# controllerHat.net
KiCad netlist of a schematic drawn in EAGLE
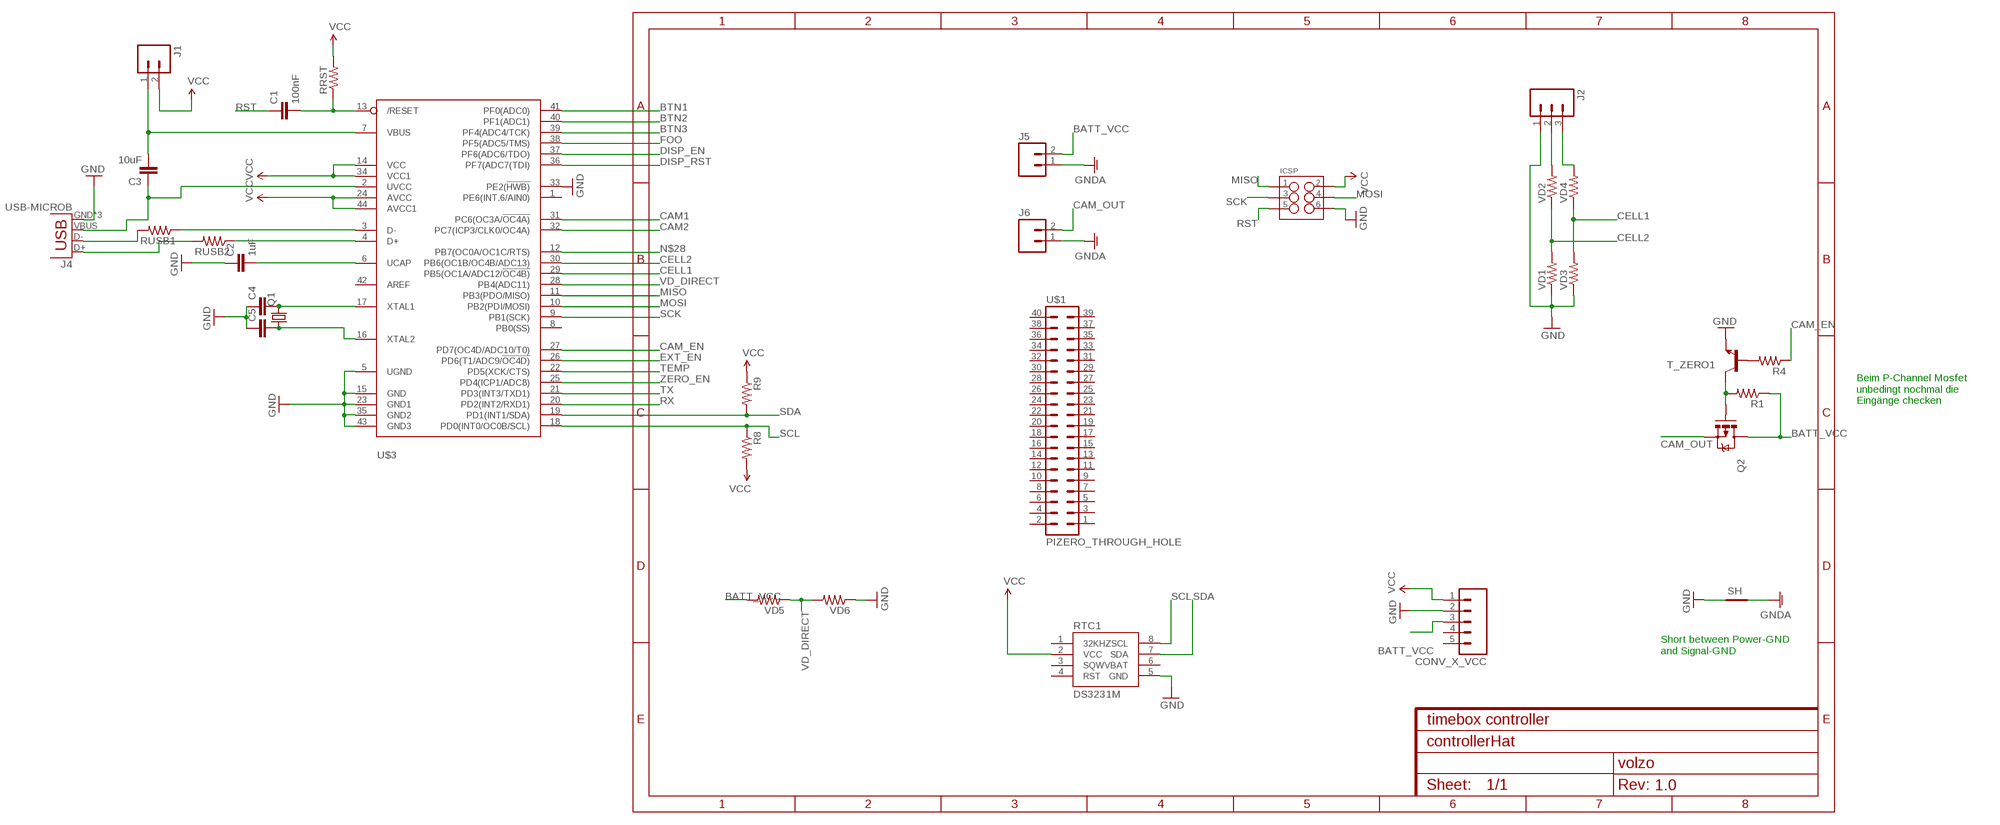
[diagram p0: schematic, sheet 1]

(export (version "E")
  (design (tool "Eeschema 10.0.6"))
  (components
    (comp (ref "C1")
      (value "100nF")
      (footprint "eagle-import:1206")
      (libsource (lib "eagle-import") (part "SparkFun-Passives_CAP1206"))
    )
    (comp (ref "C2")
      (value "1uF")
      (footprint "eagle-import:1206")
      (libsource (lib "eagle-import") (part "CAP1206"))
    )
    (comp (ref "C3")
      (value "10uF")
      (footprint "eagle-import:1206")
      (libsource (lib "eagle-import") (part "SparkFun-Passives_CAP1206"))
    )
    (comp (ref "C4")
      (value "CAP1206")
      (footprint "eagle-import:1206")
      (libsource (lib "eagle-import") (part "SparkFun-Passives_CAP1206"))
    )
    (comp (ref "C5")
      (value "CAP1206")
      (footprint "eagle-import:1206")
      (libsource (lib "eagle-import") (part "SparkFun-Passives_CAP1206"))
    )
    (comp (ref "CONV_X_VCC")
      (value "M05LOCK")
      (footprint "eagle-import:1X05_LOCK")
      (libsource (lib "eagle-import") (part "M05LOCK"))
    )
    (comp (ref "ICSP")
      (value "M03X2FEMALE")
      (footprint "eagle-import:2X3")
      (libsource (lib "eagle-import") (part "M03X2FEMALE"))
    )
    (comp (ref "J1")
      (value "M02LOCK")
      (footprint "eagle-import:1X02_LOCK")
      (libsource (lib "eagle-import") (part "M02LOCK"))
    )
    (comp (ref "J2")
      (value "M03LOCK")
      (footprint "eagle-import:1X03_LOCK")
      (libsource (lib "eagle-import") (part "M03LOCK"))
    )
    (comp (ref "J4")
      (value "USB-MICROB")
      (footprint "eagle-import:USB-MICROB")
      (libsource (lib "eagle-import") (part "USB-MICROB"))
    )
    (comp (ref "J5")
      (value "M023.5MM_LOCK")
      (footprint "eagle-import:SCREWTERMINAL-3.5MM-2_LOCK")
      (libsource (lib "eagle-import") (part "M023.5MM_LOCK"))
    )
    (comp (ref "J6")
      (value "M023.5MM_LOCK")
      (footprint "eagle-import:SCREWTERMINAL-3.5MM-2_LOCK")
      (libsource (lib "eagle-import") (part "M023.5MM_LOCK"))
    )
    (comp (ref "Q1")
      (value "CRYSTALMM20SS")
      (footprint "eagle-import:MM20SS")
      (libsource (lib "eagle-import") (part "CRYSTALMM20SS"))
    )
    (comp (ref "Q2")
      (value "MOSFET-PCHANNELNDP6020P_20V_24A_LOW_VGS_TH")
      (footprint "eagle-import:TO220V")
      (libsource (lib "eagle-import") (part "MOSFET-PCHANNELNDP6020P_20V_24A_LOW_VGS_TH"))
    )
    (comp (ref "R1")
      (value "RESISTOR1206")
      (footprint "eagle-import:1206")
      (libsource (lib "eagle-import") (part "RESISTOR1206"))
    )
    (comp (ref "R4")
      (value "RESISTOR1206")
      (footprint "eagle-import:1206")
      (libsource (lib "eagle-import") (part "RESISTOR1206"))
    )
    (comp (ref "R8")
      (value "RESISTOR1206")
      (footprint "eagle-import:1206")
      (libsource (lib "eagle-import") (part "RESISTOR1206"))
    )
    (comp (ref "R9")
      (value "RESISTOR1206")
      (footprint "eagle-import:1206")
      (libsource (lib "eagle-import") (part "RESISTOR1206"))
    )
    (comp (ref "RRST")
      (value "RESISTOR1206")
      (footprint "eagle-import:1206")
      (libsource (lib "eagle-import") (part "RESISTOR1206"))
    )
    (comp (ref "RTC1")
      (value "DS3231M")
      (footprint "eagle-import:SOIC8")
      (libsource (lib "eagle-import") (part "DS3231M"))
    )
    (comp (ref "RUSB1")
      (value "RESISTOR1206")
      (footprint "eagle-import:1206")
      (libsource (lib "eagle-import") (part "RESISTOR1206"))
    )
    (comp (ref "RUSB2")
      (value "RESISTOR1206")
      (footprint "eagle-import:1206")
      (libsource (lib "eagle-import") (part "RESISTOR1206"))
    )
    (comp (ref "SH")
      (value "SHORT-HT5")
      (footprint "eagle-import:SHORT_TOP-50")
      (libsource (lib "eagle-import") (part "SHORT-HT5"))
    )
    (comp (ref "T_ZERO1")
      (value "TRANSISTOR_NPN2N3904")
      (footprint "eagle-import:TO-92")
      (libsource (lib "eagle-import") (part "TRANSISTOR_NPN2N3904"))
    )
    (comp (ref "U$1")
      (value "PIZERO_THROUGH_HOLE")
      (footprint "eagle-import:PIZERO_THOUGH_HOLE")
      (libsource (lib "eagle-import") (part "PIZERO_THROUGH_HOLE"))
    )
    (comp (ref "U$3")
      (value "ATMEGA32U4-AU")
      (footprint "eagle-import:TQFP44")
      (libsource (lib "eagle-import") (part "ATMEGA32U4-AU"))
    )
    (comp (ref "VD1")
      (value "RESISTOR1206")
      (footprint "eagle-import:1206")
      (libsource (lib "eagle-import") (part "RESISTOR1206"))
    )
    (comp (ref "VD2")
      (value "RESISTOR1206")
      (footprint "eagle-import:1206")
      (libsource (lib "eagle-import") (part "RESISTOR1206"))
    )
    (comp (ref "VD3")
      (value "RESISTOR1206")
      (footprint "eagle-import:1206")
      (libsource (lib "eagle-import") (part "RESISTOR1206"))
    )
    (comp (ref "VD4")
      (value "RESISTOR1206")
      (footprint "eagle-import:1206")
      (libsource (lib "eagle-import") (part "RESISTOR1206"))
    )
    (comp (ref "VD5")
      (value "RESISTOR1206")
      (footprint "eagle-import:1206")
      (libsource (lib "eagle-import") (part "RESISTOR1206"))
    )
    (comp (ref "VD6")
      (value "RESISTOR1206")
      (footprint "eagle-import:1206")
      (libsource (lib "eagle-import") (part "RESISTOR1206"))
    )
  )
  (nets
    (net (code "1") (name "/BATT_VCC") (class "Default")
      (node (ref "CONV_X_VCC") (pin "3") (pinfunction "3_3") (pintype "passive"))
      (node (ref "J5") (pin "2") (pinfunction "2_2") (pintype "passive"))
      (node (ref "Q2") (pin "2") (pinfunction "D_2") (pintype "passive"))
      (node (ref "R1") (pin "1") (pinfunction "1_1") (pintype "passive"))
      (node (ref "VD5") (pin "2") (pinfunction "2_2") (pintype "passive"))
    )
    (net (code "2") (name "/BTN1") (class "Default")
      (node (ref "U$3") (pin "41") (pinfunction "PF0(ADC0)_41") (pintype "bidirectional"))
    )
    (net (code "3") (name "/BTN2") (class "Default")
      (node (ref "U$3") (pin "40") (pinfunction "PF1(ADC1)_40") (pintype "bidirectional"))
    )
    (net (code "4") (name "/BTN3") (class "Default")
      (node (ref "U$3") (pin "39") (pinfunction "PF4(ADC4/TCK)_39") (pintype "bidirectional"))
    )
    (net (code "5") (name "/CAM1") (class "Default")
      (node (ref "U$3") (pin "31") (pinfunction "PC6(OC3A/~{OC4A})_31") (pintype "bidirectional"))
    )
    (net (code "6") (name "/CAM2") (class "Default")
      (node (ref "U$3") (pin "32") (pinfunction "PC7(ICP3/CLK0/OC4A)_32") (pintype "bidirectional"))
    )
    (net (code "7") (name "/CAM_EN") (class "Default")
      (node (ref "R4") (pin "1") (pinfunction "1_1") (pintype "passive"))
      (node (ref "U$3") (pin "27") (pinfunction "PD7(OC4D/ADC10/T0)_27") (pintype "bidirectional"))
    )
    (net (code "8") (name "/CAM_OUT") (class "Default")
      (node (ref "J6") (pin "2") (pinfunction "2_2") (pintype "passive"))
      (node (ref "Q2") (pin "3") (pinfunction "S_3") (pintype "passive"))
    )
    (net (code "9") (name "/CELL1") (class "Default")
      (node (ref "U$3") (pin "29") (pinfunction "PB5(OC1A/ADC12/~{OC4B})_29") (pintype "bidirectional"))
      (node (ref "VD3") (pin "2") (pinfunction "2_2") (pintype "passive"))
      (node (ref "VD4") (pin "1") (pinfunction "1_1") (pintype "passive"))
    )
    (net (code "10") (name "/CELL2") (class "Default")
      (node (ref "U$3") (pin "30") (pinfunction "PB6(OC1B/OC4B/ADC13)_30") (pintype "bidirectional"))
      (node (ref "VD1") (pin "2") (pinfunction "2_2") (pintype "passive"))
      (node (ref "VD2") (pin "1") (pinfunction "1_1") (pintype "passive"))
    )
    (net (code "11") (name "/DISP_EN") (class "Default")
      (node (ref "U$3") (pin "37") (pinfunction "PF6(ADC6/TDO)_37") (pintype "bidirectional"))
    )
    (net (code "12") (name "/DISP_RST") (class "Default")
      (node (ref "U$3") (pin "36") (pinfunction "PF7(ADC7(TDI)_36") (pintype "bidirectional"))
    )
    (net (code "13") (name "/EXT_EN") (class "Default")
      (node (ref "U$3") (pin "26") (pinfunction "PD6(T1/ADC9/~{OC4D})_26") (pintype "bidirectional"))
    )
    (net (code "14") (name "/FOO") (class "Default")
      (node (ref "U$3") (pin "38") (pinfunction "PF5(ADC5/TMS)_38") (pintype "bidirectional"))
    )
    (net (code "15") (name "/MISO") (class "Default")
      (node (ref "ICSP") (pin "1") (pinfunction "1_1") (pintype "bidirectional"))
      (node (ref "U$3") (pin "11") (pinfunction "PB3(PDO/MISO)_11") (pintype "bidirectional"))
    )
    (net (code "16") (name "/MOSI") (class "Default")
      (node (ref "ICSP") (pin "4") (pinfunction "4_4") (pintype "bidirectional"))
      (node (ref "U$3") (pin "10") (pinfunction "PB2(PDI/MOSI)_10") (pintype "bidirectional"))
    )
    (net (code "17") (name "/N$28") (class "Default")
      (node (ref "U$3") (pin "12") (pinfunction "PB7(OC0A/OC1C/RTS)_12") (pintype "bidirectional"))
    )
    (net (code "18") (name "/RST") (class "Default")
      (node (ref "C1") (pin "1") (pinfunction "1_1") (pintype "passive"))
      (node (ref "ICSP") (pin "5") (pinfunction "5_5") (pintype "bidirectional"))
    )
    (net (code "19") (name "/RX") (class "Default")
      (node (ref "U$3") (pin "20") (pinfunction "PD2(INT2/RXD1)_20") (pintype "bidirectional"))
    )
    (net (code "20") (name "/SCK") (class "Default")
      (node (ref "ICSP") (pin "3") (pinfunction "3_3") (pintype "bidirectional"))
      (node (ref "U$3") (pin "9") (pinfunction "PB1(SCK)_9") (pintype "bidirectional"))
    )
    (net (code "21") (name "/SCL") (class "Default")
      (node (ref "R8") (pin "1") (pinfunction "1_1") (pintype "passive"))
      (node (ref "RTC1") (pin "8") (pinfunction "SCL_8") (pintype "bidirectional"))
      (node (ref "U$3") (pin "18") (pinfunction "PD0(INT0/OC0B/SCL)_18") (pintype "bidirectional"))
    )
    (net (code "22") (name "/SDA") (class "Default")
      (node (ref "R9") (pin "2") (pinfunction "2_2") (pintype "passive"))
      (node (ref "RTC1") (pin "7") (pinfunction "SDA_7") (pintype "bidirectional"))
      (node (ref "U$3") (pin "19") (pinfunction "PD1(INT1/SDA)_19") (pintype "bidirectional"))
    )
    (net (code "23") (name "/TEMP") (class "Default")
      (node (ref "U$3") (pin "22") (pinfunction "PD5(XCK/CTS)_22") (pintype "bidirectional"))
    )
    (net (code "24") (name "/TX") (class "Default")
      (node (ref "U$3") (pin "21") (pinfunction "PD3(INT3/TXD1)_21") (pintype "bidirectional"))
    )
    (net (code "25") (name "/VBAT") (class "Default")
      (node (ref "RTC1") (pin "6") (pinfunction "VBAT_6") (pintype "power_in"))
    )
    (net (code "26") (name "/VD_DIRECT") (class "Default")
      (node (ref "U$3") (pin "28") (pinfunction "PB4(ADC11)_28") (pintype "bidirectional"))
      (node (ref "VD5") (pin "1") (pinfunction "1_1") (pintype "passive"))
      (node (ref "VD6") (pin "2") (pinfunction "2_2") (pintype "passive"))
    )
    (net (code "27") (name "/ZERO_EN") (class "Default")
      (node (ref "U$3") (pin "25") (pinfunction "PD4(ICP1/ADC8)_25") (pintype "bidirectional"))
    )
    (net (code "28") (name "GND") (class "Default")
      (node (ref "C2") (pin "1") (pinfunction "1_1") (pintype "passive"))
      (node (ref "C4") (pin "1") (pinfunction "1_1") (pintype "passive"))
      (node (ref "C5") (pin "1") (pinfunction "1_1") (pintype "passive"))
      (node (ref "CONV_X_VCC") (pin "2") (pinfunction "2_2") (pintype "passive"))
      (node (ref "ICSP") (pin "6") (pinfunction "6_6") (pintype "bidirectional"))
      (node (ref "J2") (pin "1") (pinfunction "1_1") (pintype "passive"))
      (node (ref "J4") (pin "GND") (pinfunction "GND_GND") (pintype "bidirectional"))
      (node (ref "J4") (pin "MT1") (pinfunction "GND_MT1") (pintype "bidirectional"))
      (node (ref "J4") (pin "MT2") (pinfunction "GND_MT2") (pintype "bidirectional"))
      (node (ref "RTC1") (pin "5") (pinfunction "GND_5") (pintype "power_in"))
      (node (ref "SH") (pin "1") (pinfunction "P$1_1") (pintype "bidirectional"))
      (node (ref "T_ZERO1") (pin "1") (pinfunction "E_1") (pintype "passive"))
      (node (ref "U$3") (pin "15") (pinfunction "GND_15") (pintype "bidirectional"))
      (node (ref "U$3") (pin "23") (pinfunction "GND1_23") (pintype "bidirectional"))
      (node (ref "U$3") (pin "33") (pinfunction "PE2(~{HWB})_33") (pintype "bidirectional"))
      (node (ref "U$3") (pin "35") (pinfunction "GND2_35") (pintype "bidirectional"))
      (node (ref "U$3") (pin "43") (pinfunction "GND3_43") (pintype "bidirectional"))
      (node (ref "U$3") (pin "5") (pinfunction "UGND_5") (pintype "bidirectional"))
      (node (ref "VD1") (pin "1") (pinfunction "1_1") (pintype "passive"))
      (node (ref "VD3") (pin "1") (pinfunction "1_1") (pintype "passive"))
      (node (ref "VD6") (pin "1") (pinfunction "1_1") (pintype "passive"))
    )
    (net (code "29") (name "GNDA") (class "Default")
      (node (ref "J5") (pin "1") (pinfunction "1_1") (pintype "passive"))
      (node (ref "J6") (pin "1") (pinfunction "1_1") (pintype "passive"))
      (node (ref "SH") (pin "2") (pinfunction "P$2_2") (pintype "bidirectional"))
    )
    (net (code "30") (name "Net-(J2-Pad2)") (class "Default")
      (node (ref "J2") (pin "2") (pinfunction "2_2") (pintype "passive"))
      (node (ref "VD2") (pin "2") (pinfunction "2_2") (pintype "passive"))
    )
    (net (code "31") (name "Net-(J2-Pad3)") (class "Default")
      (node (ref "J2") (pin "3") (pinfunction "3_3") (pintype "passive"))
      (node (ref "VD4") (pin "2") (pinfunction "2_2") (pintype "passive"))
    )
    (net (code "32") (name "Net-(J4-PadD+)") (class "Default")
      (node (ref "J4") (pin "D+") (pinfunction "D+_D+") (pintype "bidirectional"))
      (node (ref "RUSB2") (pin "2") (pinfunction "2_2") (pintype "passive"))
    )
    (net (code "33") (name "Net-(J4-PadD-)") (class "Default")
      (node (ref "J4") (pin "D-") (pinfunction "D-_D-") (pintype "bidirectional"))
      (node (ref "RUSB1") (pin "2") (pinfunction "2_2") (pintype "passive"))
    )
    (net (code "34") (name "Net-(Q1-2)") (class "Default")
      (node (ref "C4") (pin "2") (pinfunction "2_2") (pintype "passive"))
      (node (ref "Q1") (pin "4") (pinfunction "2_4") (pintype "passive"))
      (node (ref "U$3") (pin "17") (pinfunction "XTAL1_17") (pintype "bidirectional"))
    )
    (net (code "35") (name "Net-(Q2-G)") (class "Default")
      (node (ref "Q2") (pin "1") (pinfunction "G_1") (pintype "passive"))
      (node (ref "R1") (pin "2") (pinfunction "2_2") (pintype "passive"))
      (node (ref "T_ZERO1") (pin "3") (pinfunction "C_3") (pintype "passive"))
    )
    (net (code "36") (name "Net-(T_ZERO1-B)") (class "Default")
      (node (ref "R4") (pin "2") (pinfunction "2_2") (pintype "passive"))
      (node (ref "T_ZERO1") (pin "2") (pinfunction "B_2") (pintype "passive"))
    )
    (net (code "37") (name "Net-(U$3-D+)") (class "Default")
      (node (ref "RUSB2") (pin "1") (pinfunction "1_1") (pintype "passive"))
      (node (ref "U$3") (pin "4") (pinfunction "D+_4") (pintype "bidirectional"))
    )
    (net (code "38") (name "Net-(U$3-D-)") (class "Default")
      (node (ref "RUSB1") (pin "1") (pinfunction "1_1") (pintype "passive"))
      (node (ref "U$3") (pin "3") (pinfunction "D-_3") (pintype "bidirectional"))
    )
    (net (code "39") (name "Net-(U$3-UCAP)") (class "Default")
      (node (ref "C2") (pin "2") (pinfunction "2_2") (pintype "passive"))
      (node (ref "U$3") (pin "6") (pinfunction "UCAP_6") (pintype "bidirectional"))
    )
    (net (code "40") (name "Net-(U$3-UVCC)") (class "Default")
      (node (ref "C3") (pin "1") (pinfunction "1_1") (pintype "passive"))
      (node (ref "J4") (pin "VBUS") (pinfunction "VBUS_VBUS") (pintype "bidirectional"))
      (node (ref "U$3") (pin "2") (pinfunction "UVCC_2") (pintype "bidirectional"))
    )
    (net (code "41") (name "Net-(U$3-VBUS)") (class "Default")
      (node (ref "C3") (pin "2") (pinfunction "2_2") (pintype "passive"))
      (node (ref "J1") (pin "1") (pinfunction "1_1") (pintype "passive"))
      (node (ref "U$3") (pin "7") (pinfunction "VBUS_7") (pintype "bidirectional"))
    )
    (net (code "42") (name "Net-(U$3-XTAL2)") (class "Default")
      (node (ref "C5") (pin "2") (pinfunction "2_2") (pintype "passive"))
      (node (ref "Q1") (pin "1") (pinfunction "1_1") (pintype "passive"))
      (node (ref "U$3") (pin "16") (pinfunction "XTAL2_16") (pintype "bidirectional"))
    )
    (net (code "43") (name "Net-(U$3-{slash}RESET)") (class "Default")
      (node (ref "C1") (pin "2") (pinfunction "2_2") (pintype "passive"))
      (node (ref "RRST") (pin "1") (pinfunction "1_1") (pintype "passive"))
      (node (ref "U$3") (pin "13") (pinfunction "/RESET_13") (pintype "bidirectional"))
    )
    (net (code "44") (name "VCC") (class "Default")
      (node (ref "CONV_X_VCC") (pin "1") (pinfunction "1_1") (pintype "passive"))
      (node (ref "ICSP") (pin "2") (pinfunction "2_2") (pintype "bidirectional"))
      (node (ref "J1") (pin "2") (pinfunction "2_2") (pintype "passive"))
      (node (ref "R8") (pin "2") (pinfunction "2_2") (pintype "passive"))
      (node (ref "R9") (pin "1") (pinfunction "1_1") (pintype "passive"))
      (node (ref "RRST") (pin "2") (pinfunction "2_2") (pintype "passive"))
      (node (ref "RTC1") (pin "2") (pinfunction "VCC_2") (pintype "power_in"))
      (node (ref "U$3") (pin "14") (pinfunction "VCC_14") (pintype "bidirectional"))
      (node (ref "U$3") (pin "24") (pinfunction "AVCC_24") (pintype "bidirectional"))
      (node (ref "U$3") (pin "34") (pinfunction "VCC1_34") (pintype "bidirectional"))
      (node (ref "U$3") (pin "44") (pinfunction "AVCC1_44") (pintype "bidirectional"))
    )
    (net (code "45") (name "unconnected-(CONV_X_VCC-Pad4)") (class "Default")
      (node (ref "CONV_X_VCC") (pin "4") (pinfunction "4_4") (pintype "passive"))
    )
    (net (code "46") (name "unconnected-(CONV_X_VCC-Pad5)") (class "Default")
      (node (ref "CONV_X_VCC") (pin "5") (pinfunction "5_5") (pintype "passive"))
    )
    (net (code "47") (name "unconnected-(RTC1-32KHZ-Pad1)") (class "Default")
      (node (ref "RTC1") (pin "1") (pinfunction "32KHZ_1") (pintype "output"))
    )
    (net (code "48") (name "unconnected-(RTC1-RST-Pad4)") (class "Default")
      (node (ref "RTC1") (pin "4") (pinfunction "RST_4") (pintype "bidirectional"))
    )
    (net (code "49") (name "unconnected-(RTC1-SQW-Pad3)") (class "Default")
      (node (ref "RTC1") (pin "3") (pinfunction "SQW_3") (pintype "output"))
    )
    (net (code "50") (name "unconnected-(U$1-Pad1)") (class "Default")
      (node (ref "U$1") (pin "1") (pinfunction "1_1") (pintype "passive"))
    )
    (net (code "51") (name "unconnected-(U$1-Pad2)") (class "Default")
      (node (ref "U$1") (pin "2") (pinfunction "2_2") (pintype "passive"))
    )
    (net (code "52") (name "unconnected-(U$1-Pad3)") (class "Default")
      (node (ref "U$1") (pin "3") (pinfunction "3_3") (pintype "passive"))
    )
    (net (code "53") (name "unconnected-(U$1-Pad4)") (class "Default")
      (node (ref "U$1") (pin "4") (pinfunction "4_4") (pintype "passive"))
    )
    (net (code "54") (name "unconnected-(U$1-Pad5)") (class "Default")
      (node (ref "U$1") (pin "5") (pinfunction "5_5") (pintype "passive"))
    )
    (net (code "55") (name "unconnected-(U$1-Pad6)") (class "Default")
      (node (ref "U$1") (pin "6") (pinfunction "6_6") (pintype "passive"))
    )
    (net (code "56") (name "unconnected-(U$1-Pad7)") (class "Default")
      (node (ref "U$1") (pin "7") (pinfunction "7_7") (pintype "passive"))
    )
    (net (code "57") (name "unconnected-(U$1-Pad8)") (class "Default")
      (node (ref "U$1") (pin "8") (pinfunction "8_8") (pintype "passive"))
    )
    (net (code "58") (name "unconnected-(U$1-Pad9)") (class "Default")
      (node (ref "U$1") (pin "9") (pinfunction "9_9") (pintype "passive"))
    )
    (net (code "59") (name "unconnected-(U$1-Pad10)") (class "Default")
      (node (ref "U$1") (pin "10") (pinfunction "10_10") (pintype "passive"))
    )
    (net (code "60") (name "unconnected-(U$1-Pad11)") (class "Default")
      (node (ref "U$1") (pin "11") (pinfunction "11_11") (pintype "passive"))
    )
    (net (code "61") (name "unconnected-(U$1-Pad12)") (class "Default")
      (node (ref "U$1") (pin "12") (pinfunction "12_12") (pintype "passive"))
    )
    (net (code "62") (name "unconnected-(U$1-Pad13)") (class "Default")
      (node (ref "U$1") (pin "13") (pinfunction "13_13") (pintype "passive"))
    )
    (net (code "63") (name "unconnected-(U$1-Pad14)") (class "Default")
      (node (ref "U$1") (pin "14") (pinfunction "14_14") (pintype "passive"))
    )
    (net (code "64") (name "unconnected-(U$1-Pad15)") (class "Default")
      (node (ref "U$1") (pin "15") (pinfunction "15_15") (pintype "passive"))
    )
    (net (code "65") (name "unconnected-(U$1-Pad16)") (class "Default")
      (node (ref "U$1") (pin "16") (pinfunction "16_16") (pintype "passive"))
    )
    (net (code "66") (name "unconnected-(U$1-Pad17)") (class "Default")
      (node (ref "U$1") (pin "17") (pinfunction "17_17") (pintype "passive"))
    )
    (net (code "67") (name "unconnected-(U$1-Pad18)") (class "Default")
      (node (ref "U$1") (pin "18") (pinfunction "18_18") (pintype "passive"))
    )
    (net (code "68") (name "unconnected-(U$1-Pad19)") (class "Default")
      (node (ref "U$1") (pin "19") (pinfunction "19_19") (pintype "passive"))
    )
    (net (code "69") (name "unconnected-(U$1-Pad20)") (class "Default")
      (node (ref "U$1") (pin "20") (pinfunction "20_20") (pintype "passive"))
    )
    (net (code "70") (name "unconnected-(U$1-Pad21)") (class "Default")
      (node (ref "U$1") (pin "21") (pinfunction "21_21") (pintype "passive"))
    )
    (net (code "71") (name "unconnected-(U$1-Pad22)") (class "Default")
      (node (ref "U$1") (pin "22") (pinfunction "22_22") (pintype "passive"))
    )
    (net (code "72") (name "unconnected-(U$1-Pad23)") (class "Default")
      (node (ref "U$1") (pin "23") (pinfunction "23_23") (pintype "passive"))
    )
    (net (code "73") (name "unconnected-(U$1-Pad24)") (class "Default")
      (node (ref "U$1") (pin "24") (pinfunction "24_24") (pintype "passive"))
    )
    (net (code "74") (name "unconnected-(U$1-Pad25)") (class "Default")
      (node (ref "U$1") (pin "25") (pinfunction "25_25") (pintype "passive"))
    )
    (net (code "75") (name "unconnected-(U$1-Pad26)") (class "Default")
      (node (ref "U$1") (pin "26") (pinfunction "26_26") (pintype "passive"))
    )
    (net (code "76") (name "unconnected-(U$1-Pad27)") (class "Default")
      (node (ref "U$1") (pin "27") (pinfunction "27_27") (pintype "passive"))
    )
    (net (code "77") (name "unconnected-(U$1-Pad28)") (class "Default")
      (node (ref "U$1") (pin "28") (pinfunction "28_28") (pintype "passive"))
    )
    (net (code "78") (name "unconnected-(U$1-Pad29)") (class "Default")
      (node (ref "U$1") (pin "29") (pinfunction "29_29") (pintype "passive"))
    )
    (net (code "79") (name "unconnected-(U$1-Pad30)") (class "Default")
      (node (ref "U$1") (pin "30") (pinfunction "30_30") (pintype "passive"))
    )
    (net (code "80") (name "unconnected-(U$1-Pad31)") (class "Default")
      (node (ref "U$1") (pin "31") (pinfunction "31_31") (pintype "passive"))
    )
    (net (code "81") (name "unconnected-(U$1-Pad32)") (class "Default")
      (node (ref "U$1") (pin "32") (pinfunction "32_32") (pintype "passive"))
    )
    (net (code "82") (name "unconnected-(U$1-Pad33)") (class "Default")
      (node (ref "U$1") (pin "33") (pinfunction "33_33") (pintype "passive"))
    )
    (net (code "83") (name "unconnected-(U$1-Pad34)") (class "Default")
      (node (ref "U$1") (pin "34") (pinfunction "34_34") (pintype "passive"))
    )
    (net (code "84") (name "unconnected-(U$1-Pad35)") (class "Default")
      (node (ref "U$1") (pin "35") (pinfunction "35_35") (pintype "passive"))
    )
    (net (code "85") (name "unconnected-(U$1-Pad36)") (class "Default")
      (node (ref "U$1") (pin "36") (pinfunction "36_36") (pintype "passive"))
    )
    (net (code "86") (name "unconnected-(U$1-Pad37)") (class "Default")
      (node (ref "U$1") (pin "37") (pinfunction "37_37") (pintype "passive"))
    )
    (net (code "87") (name "unconnected-(U$1-Pad38)") (class "Default")
      (node (ref "U$1") (pin "38") (pinfunction "38_38") (pintype "passive"))
    )
    (net (code "88") (name "unconnected-(U$1-Pad39)") (class "Default")
      (node (ref "U$1") (pin "39") (pinfunction "39_39") (pintype "passive"))
    )
    (net (code "89") (name "unconnected-(U$1-Pad40)") (class "Default")
      (node (ref "U$1") (pin "40") (pinfunction "40_40") (pintype "passive"))
    )
    (net (code "90") (name "unconnected-(U$3-AREF-Pad42)") (class "Default")
      (node (ref "U$3") (pin "42") (pinfunction "AREF_42") (pintype "bidirectional"))
    )
    (net (code "91") (name "unconnected-(U$3-PB0(SS)-Pad8)") (class "Default")
      (node (ref "U$3") (pin "8") (pinfunction "PB0(SS)_8") (pintype "bidirectional"))
    )
    (net (code "92") (name "unconnected-(U$3-PE6(INT.6{slash}AIN0)-Pad1)") (class "Default")
      (node (ref "U$3") (pin "1") (pinfunction "PE6(INT.6/AIN0)_1") (pintype "bidirectional"))
    )
  )
)
